# DD2090_4CAM_FFC_Connector_A.net
KiCad netlist of a schematic drawn in Altium Designer
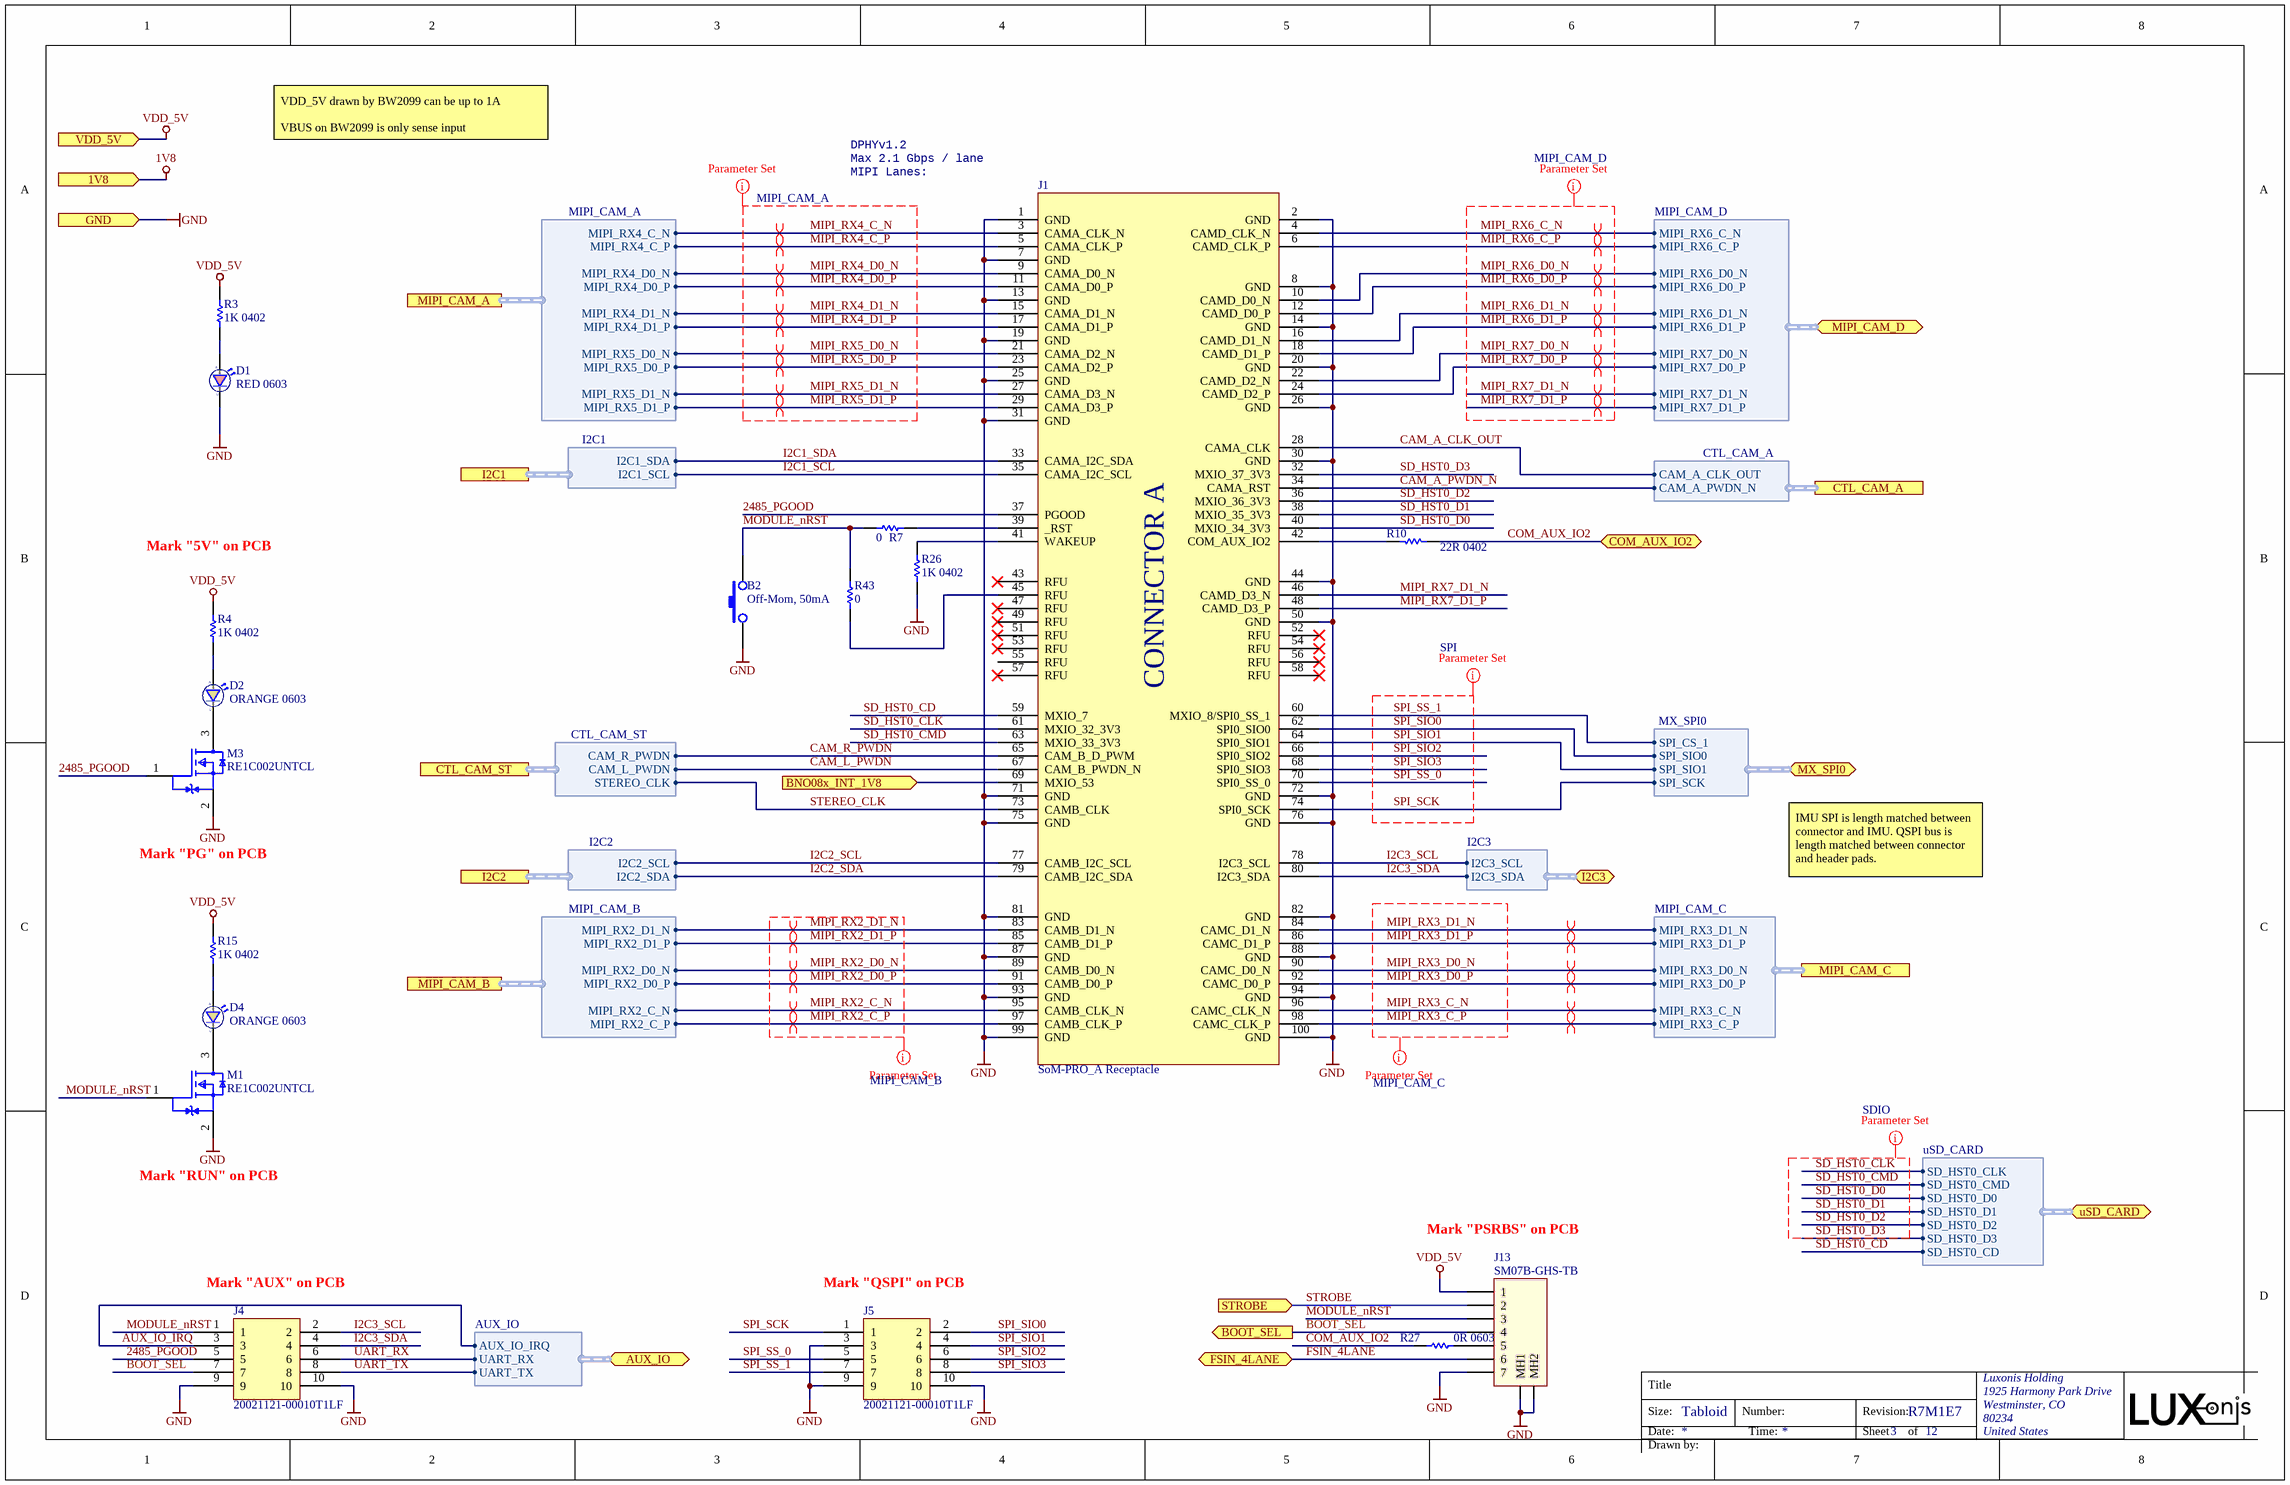
[diagram p0: DD2090_4CAM_FFC_Connector_A.SchDoc]

(export (version "E")
  (design (tool "Eeschema 10.0.6"))
  (components
    (comp (ref "B2")
      (value "Off-Mom, 50mA")
      (footprint "LuxonisMaster:DTSM-32N-V")
      (description "SWITCH TACTILE SMT 3.5mm * 6mm , brown 160gf")
      (libsource (lib "LuxonisMaster") (part "DTSM-32N-V"))
    )
    (comp (ref "D1")
      (value "RED 0603")
      (footprint "LuxonisMaster:SML_D1xx8W")
      (description "LED RED DIFFUSED 0603 SMD Red 620nm LED Indication - Discrete 2.2V 0603 (1608 Metric)")
      (libsource (lib "LuxonisMaster") (part "SML-D12U8WT86"))
    )
    (comp (ref "D2")
      (value "ORANGE 0603")
      (footprint "LuxonisMaster:SML_D1xx8W")
      (description "LED ORANGE DIFFUSED 0603 SMD Orange 605nm LED Indication - Discrete 2.2V 0603 (1608 Metric)")
      (libsource (lib "LuxonisMaster") (part "SML-D12D8WT86"))
    )
    (comp (ref "D4")
      (value "ORANGE 0603")
      (footprint "LuxonisMaster:SML_D1xx8W")
      (description "LED ORANGE DIFFUSED 0603 SMD Orange 605nm LED Indication - Discrete 2.2V 0603 (1608 Metric)")
      (libsource (lib "LuxonisMaster") (part "SML-D12D8WT86"))
    )
    (comp (ref "J1")
      (value "SoM-PRO_A Receptacle")
      (footprint "LuxonisMaster:CON_A_BW2099_SoM_DF40HC-3.0-100DS-0.4V_minpad")
      (description "CONN RCPT 100POS 0.4MM SMD GOLD")
      (libsource (lib "LuxonisMaster") (part "DF40HC(3.0)-100DS-0.4V_SoM-PRO_A"))
    )
    (comp (ref "J4")
      (value "20021121-00010T1LF")
      (footprint "LuxonisMaster:20021121-00010T1LF")
      (description "CONN HEADER SMD 10POS 1.27MM")
      (libsource (lib "LuxonisMaster") (part "20021121-00010T1LF"))
    )
    (comp (ref "J5")
      (value "20021121-00010T1LF")
      (footprint "LuxonisMaster:20021121-00010T1LF")
      (description "CONN HEADER SMD 10POS 1.27MM")
      (libsource (lib "LuxonisMaster") (part "20021121-00010T1LF"))
    )
    (comp (ref "J13")
      (value "SM07B-GHS-TB")
      (footprint "SM07B-GHS-TB")
      (description "Conn Shrouded Header HDR 7 POS 1.25mm Solder RA Side Entry SMD T/R")
      (libsource (lib "DD2090_4CAM_FFC") (part "SM07B-GHS-TB(LF)(SN)"))
    )
    (comp (ref "M1")
      (value "RE1C002UNTCL")
      (footprint "LuxonisMaster:RE1C002UNTCL")
      (description "MOSFET N-CH 20V 0.2A EMT3")
      (libsource (lib "LuxonisMaster") (part "RE1C002UNTCL"))
    )
    (comp (ref "M3")
      (value "RE1C002UNTCL")
      (footprint "LuxonisMaster:RE1C002UNTCL")
      (description "MOSFET N-CH 20V 0.2A EMT3")
      (libsource (lib "LuxonisMaster") (part "RE1C002UNTCL"))
    )
    (comp (ref "R3")
      (value "1K 0402")
      (footprint "RES_Altium_Vault_Generic:RESC0402(1005)_N")
      (fields (field (name "TOLERANCE") "1%"))
      (libsource (lib "LuxonisMaster") (part "RC0402FR-071KL"))
    )
    (comp (ref "R4")
      (value "1K 0402")
      (footprint "RES_Altium_Vault_Generic:RESC0402(1005)_N")
      (fields (field (name "TOLERANCE") "1%"))
      (libsource (lib "LuxonisMaster") (part "RC0402FR-071KL"))
    )
    (comp (ref "R7")
      (value "0")
      (footprint "RESC0402(1005)_L")
      (description "RES SMD 0 OHM JUMPER 1/16W 0402")
      (fields (field (name "TOLERANCE") "5%") (field (name "Comment") "CRCW04020000Z0ED"))
      (libsource (lib "Luxonis LLC") (part "CR0402-FX-2492GLF"))
    )
    (comp (ref "R10")
      (value "22R 0402")
      (footprint "RESC0402(1005)_N")
      (description "RES SMD 22 OHM 1% 1/16W 0402")
      (fields (field (name "TOLERANCE") "1%"))
      (libsource (lib "BW2098POE") (part "RC0402FR-0722RL"))
    )
    (comp (ref "R15")
      (value "1K 0402")
      (footprint "RES_Altium_Vault_Generic:RESC0402(1005)_N")
      (fields (field (name "TOLERANCE") "1%"))
      (libsource (lib "LuxonisMaster") (part "RC0402FR-071KL"))
    )
    (comp (ref "R26")
      (value "1K 0402")
      (footprint "RES_Altium_Vault_Generic:RESC0402(1005)_N")
      (fields (field (name "TOLERANCE") "1%"))
      (libsource (lib "LuxonisMaster") (part "RC0402FR-071KL"))
    )
    (comp (ref "R27")
      (value "0R 0603")
      (footprint "RESC0603(1608)_N")
      (fields (field (name "TOLERANCE") "5%"))
      (libsource (lib "LuxonisMaster") (part "CRCW06030000Z0EA"))
    )
    (comp (ref "R43")
      (value "0")
      (footprint "RESC0402(1005)_L")
      (description "RES SMD 0 OHM JUMPER 1/16W 0402")
      (fields (field (name "TOLERANCE") "5%") (field (name "Comment") "CRCW04020000Z0ED"))
      (libsource (lib "Luxonis LLC") (part "CR0402-FX-2492GLF"))
    )
  )
  (nets
    (net (code "13") (name "/2485_PGOOD") (class "Default")
      (node (ref "J1") (pin "37") (pinfunction "PGOOD_37") (pintype "passive"))
      (node (ref "J4") (pin "5") (pinfunction "5_5") (pintype "passive"))
      (node (ref "M3") (pin "1") (pinfunction "Gate_1") (pintype "passive"))
    )
    (net (code "14") (name "/AUX_IO_IRQ") (class "Default")
      (node (ref "J4") (pin "3") (pinfunction "3_3") (pintype "passive"))
    )
    (net (code "15") (name "/BNO08x_INT_1V8") (class "Default")
      (node (ref "J1") (pin "69") (pinfunction "MXIO_53_69") (pintype "passive"))
    )
    (net (code "16") (name "/BOOT_SEL") (class "Default")
      (node (ref "J13") (pin "4") (pinfunction "4_4") (pintype "passive"))
      (node (ref "J4") (pin "7") (pinfunction "7_7") (pintype "passive"))
    )
    (net (code "17") (name "/CAM_A_CLK_OUT") (class "Default")
      (node (ref "J1") (pin "28") (pinfunction "CAMA_CLK_28") (pintype "passive"))
    )
    (net (code "18") (name "/CAM_A_PWDN_N") (class "Default")
      (node (ref "J1") (pin "34") (pinfunction "CAMA_RST_34") (pintype "passive"))
    )
    (net (code "19") (name "/CAM_L_PWDN") (class "Default")
      (node (ref "J1") (pin "67") (pinfunction "CAM_B_PWDN_N_67") (pintype "passive"))
    )
    (net (code "20") (name "/CAM_R_PWDN") (class "Default")
      (node (ref "J1") (pin "65") (pinfunction "CAM_B_D_PWM_65") (pintype "passive"))
    )
    (net (code "21") (name "/COM_AUX_IO2") (class "Default")
      (node (ref "R10") (pin "1") (pinfunction "1_1") (pintype "passive"))
      (node (ref "R27") (pin "1") (pinfunction "1_1") (pintype "passive"))
    )
    (net (code "22") (name "/FSIN_4LANE") (class "Default")
      (node (ref "J13") (pin "6") (pinfunction "6_6") (pintype "passive"))
    )
    (net (code "23") (name "/I2C1_SCL") (class "Default")
      (node (ref "J1") (pin "35") (pinfunction "CAMA_I2C_SCL_35") (pintype "passive"))
    )
    (net (code "24") (name "/I2C1_SDA") (class "Default")
      (node (ref "J1") (pin "33") (pinfunction "CAMA_I2C_SDA_33") (pintype "passive"))
    )
    (net (code "25") (name "/I2C2_SCL") (class "Default")
      (node (ref "J1") (pin "77") (pinfunction "CAMB_I2C_SCL_77") (pintype "passive"))
    )
    (net (code "26") (name "/I2C2_SDA") (class "Default")
      (node (ref "J1") (pin "79") (pinfunction "CAMB_I2C_SDA_79") (pintype "passive"))
    )
    (net (code "27") (name "/I2C3_SCL") (class "Default")
      (node (ref "J1") (pin "78") (pinfunction "I2C3_SCL_78") (pintype "passive"))
      (node (ref "J4") (pin "2") (pinfunction "2_2") (pintype "passive"))
    )
    (net (code "28") (name "/I2C3_SDA") (class "Default")
      (node (ref "J1") (pin "80") (pinfunction "I2C3_SDA_80") (pintype "passive"))
      (node (ref "J4") (pin "4") (pinfunction "4_4") (pintype "passive"))
    )
    (net (code "29") (name "/MIPI_RX2_C_N") (class "Default")
      (node (ref "J1") (pin "95") (pinfunction "CAMB_CLK_N_95") (pintype "passive"))
    )
    (net (code "30") (name "/MIPI_RX2_C_P") (class "Default")
      (node (ref "J1") (pin "97") (pinfunction "CAMB_CLK_P_97") (pintype "passive"))
    )
    (net (code "31") (name "/MIPI_RX2_D0_N") (class "Default")
      (node (ref "J1") (pin "89") (pinfunction "CAMB_D0_N_89") (pintype "passive"))
    )
    (net (code "32") (name "/MIPI_RX2_D0_P") (class "Default")
      (node (ref "J1") (pin "91") (pinfunction "CAMB_D0_P_91") (pintype "passive"))
    )
    (net (code "33") (name "/MIPI_RX2_D1_N") (class "Default")
      (node (ref "J1") (pin "83") (pinfunction "CAMB_D1_N_83") (pintype "passive"))
    )
    (net (code "34") (name "/MIPI_RX2_D1_P") (class "Default")
      (node (ref "J1") (pin "85") (pinfunction "CAMB_D1_P_85") (pintype "passive"))
    )
    (net (code "35") (name "/MIPI_RX3_C_N") (class "Default")
      (node (ref "J1") (pin "96") (pinfunction "CAMC_CLK_N_96") (pintype "passive"))
    )
    (net (code "36") (name "/MIPI_RX3_C_P") (class "Default")
      (node (ref "J1") (pin "98") (pinfunction "CAMC_CLK_P_98") (pintype "passive"))
    )
    (net (code "37") (name "/MIPI_RX3_D0_N") (class "Default")
      (node (ref "J1") (pin "90") (pinfunction "CAMC_D0_N_90") (pintype "passive"))
    )
    (net (code "38") (name "/MIPI_RX3_D0_P") (class "Default")
      (node (ref "J1") (pin "92") (pinfunction "CAMC_D0_P_92") (pintype "passive"))
    )
    (net (code "39") (name "/MIPI_RX3_D1_N") (class "Default")
      (node (ref "J1") (pin "84") (pinfunction "CAMC_D1_N_84") (pintype "passive"))
    )
    (net (code "40") (name "/MIPI_RX3_D1_P") (class "Default")
      (node (ref "J1") (pin "86") (pinfunction "CAMC_D1_P_86") (pintype "passive"))
    )
    (net (code "41") (name "/MIPI_RX4_C_N") (class "Default")
      (node (ref "J1") (pin "3") (pinfunction "CAMA_CLK_N_3") (pintype "passive"))
    )
    (net (code "42") (name "/MIPI_RX4_C_P") (class "Default")
      (node (ref "J1") (pin "5") (pinfunction "CAMA_CLK_P_5") (pintype "passive"))
    )
    (net (code "43") (name "/MIPI_RX4_D0_N") (class "Default")
      (node (ref "J1") (pin "9") (pinfunction "CAMA_D0_N_9") (pintype "passive"))
    )
    (net (code "44") (name "/MIPI_RX4_D0_P") (class "Default")
      (node (ref "J1") (pin "11") (pinfunction "CAMA_D0_P_11") (pintype "passive"))
    )
    (net (code "45") (name "/MIPI_RX4_D1_N") (class "Default")
      (node (ref "J1") (pin "15") (pinfunction "CAMA_D1_N_15") (pintype "passive"))
    )
    (net (code "46") (name "/MIPI_RX4_D1_P") (class "Default")
      (node (ref "J1") (pin "17") (pinfunction "CAMA_D1_P_17") (pintype "passive"))
    )
    (net (code "47") (name "/MIPI_RX5_D0_N") (class "Default")
      (node (ref "J1") (pin "21") (pinfunction "CAMA_D2_N_21") (pintype "passive"))
    )
    (net (code "48") (name "/MIPI_RX5_D0_P") (class "Default")
      (node (ref "J1") (pin "23") (pinfunction "CAMA_D2_P_23") (pintype "passive"))
    )
    (net (code "49") (name "/MIPI_RX5_D1_N") (class "Default")
      (node (ref "J1") (pin "27") (pinfunction "CAMA_D3_N_27") (pintype "passive"))
    )
    (net (code "50") (name "/MIPI_RX5_D1_P") (class "Default")
      (node (ref "J1") (pin "29") (pinfunction "CAMA_D3_P_29") (pintype "passive"))
    )
    (net (code "51") (name "/MIPI_RX6_C_N") (class "Default")
      (node (ref "J1") (pin "4") (pinfunction "CAMD_CLK_N_4") (pintype "passive"))
    )
    (net (code "52") (name "/MIPI_RX6_C_P") (class "Default")
      (node (ref "J1") (pin "6") (pinfunction "CAMD_CLK_P_6") (pintype "passive"))
    )
    (net (code "53") (name "/MIPI_RX6_D0_N") (class "Default")
      (node (ref "J1") (pin "10") (pinfunction "CAMD_D0_N_10") (pintype "passive"))
    )
    (net (code "54") (name "/MIPI_RX6_D0_P") (class "Default")
      (node (ref "J1") (pin "12") (pinfunction "CAMD_D0_P_12") (pintype "passive"))
    )
    (net (code "55") (name "/MIPI_RX6_D1_N") (class "Default")
      (node (ref "J1") (pin "16") (pinfunction "CAMD_D1_N_16") (pintype "passive"))
    )
    (net (code "56") (name "/MIPI_RX6_D1_P") (class "Default")
      (node (ref "J1") (pin "18") (pinfunction "CAMD_D1_P_18") (pintype "passive"))
    )
    (net (code "57") (name "/MIPI_RX7_D0_N") (class "Default")
      (node (ref "J1") (pin "22") (pinfunction "CAMD_D2_N_22") (pintype "passive"))
    )
    (net (code "58") (name "/MIPI_RX7_D0_P") (class "Default")
      (node (ref "J1") (pin "24") (pinfunction "CAMD_D2_P_24") (pintype "passive"))
    )
    (net (code "59") (name "/MIPI_RX7_D1_N") (class "Default")
      (node (ref "J1") (pin "46") (pinfunction "CAMD_D3_N_46") (pintype "passive"))
    )
    (net (code "60") (name "/MIPI_RX7_D1_P") (class "Default")
      (node (ref "J1") (pin "48") (pinfunction "CAMD_D3_P_48") (pintype "passive"))
    )
    (net (code "61") (name "/MODULE_nRST") (class "Default")
      (node (ref "B2") (pin "2") (pinfunction "2_2") (pintype "passive"))
      (node (ref "J13") (pin "3") (pinfunction "3_3") (pintype "passive"))
      (node (ref "J4") (pin "1") (pinfunction "1_1") (pintype "passive"))
      (node (ref "M1") (pin "1") (pinfunction "Gate_1") (pintype "passive"))
      (node (ref "R43") (pin "2") (pinfunction "2_2") (pintype "passive"))
      (node (ref "R7") (pin "2") (pinfunction "2_2") (pintype "passive"))
    )
    (net (code "62") (name "/SD_HST0_CD") (class "Default")
      (node (ref "J1") (pin "59") (pinfunction "MXIO_7_59") (pintype "passive"))
    )
    (net (code "63") (name "/SD_HST0_CLK") (class "Default")
      (node (ref "J1") (pin "61") (pinfunction "MXIO_32_3V3_61") (pintype "passive"))
    )
    (net (code "64") (name "/SD_HST0_CMD") (class "Default")
      (node (ref "J1") (pin "63") (pinfunction "MXIO_33_3V3_63") (pintype "passive"))
    )
    (net (code "65") (name "/SD_HST0_D0") (class "Default")
      (node (ref "J1") (pin "40") (pinfunction "MXIO_34_3V3_40") (pintype "passive"))
    )
    (net (code "66") (name "/SD_HST0_D1") (class "Default")
      (node (ref "J1") (pin "38") (pinfunction "MXIO_35_3V3_38") (pintype "passive"))
    )
    (net (code "67") (name "/SD_HST0_D2") (class "Default")
      (node (ref "J1") (pin "36") (pinfunction "MXIO_36_3V3_36") (pintype "passive"))
    )
    (net (code "68") (name "/SD_HST0_D3") (class "Default")
      (node (ref "J1") (pin "32") (pinfunction "MXIO_37_3V3_32") (pintype "passive"))
    )
    (net (code "69") (name "/SPI_SCK") (class "Default")
      (node (ref "J1") (pin "74") (pinfunction "SPI0_SCK_74") (pintype "passive"))
      (node (ref "J5") (pin "1") (pinfunction "1_1") (pintype "passive"))
    )
    (net (code "70") (name "/SPI_SIO0") (class "Default")
      (node (ref "J1") (pin "62") (pinfunction "SPI0_SIO0_62") (pintype "passive"))
      (node (ref "J5") (pin "2") (pinfunction "2_2") (pintype "passive"))
    )
    (net (code "71") (name "/SPI_SIO1") (class "Default")
      (node (ref "J1") (pin "64") (pinfunction "SPI0_SIO1_64") (pintype "passive"))
      (node (ref "J5") (pin "4") (pinfunction "4_4") (pintype "passive"))
    )
    (net (code "72") (name "/SPI_SIO2") (class "Default")
      (node (ref "J1") (pin "66") (pinfunction "SPI0_SIO2_66") (pintype "passive"))
      (node (ref "J5") (pin "6") (pinfunction "6_6") (pintype "passive"))
    )
    (net (code "73") (name "/SPI_SIO3") (class "Default")
      (node (ref "J1") (pin "68") (pinfunction "SPI0_SIO3_68") (pintype "passive"))
      (node (ref "J5") (pin "8") (pinfunction "8_8") (pintype "passive"))
    )
    (net (code "74") (name "/SPI_SS_0") (class "Default")
      (node (ref "J1") (pin "70") (pinfunction "SPI0_SS_0_70") (pintype "passive"))
      (node (ref "J5") (pin "5") (pinfunction "5_5") (pintype "passive"))
    )
    (net (code "75") (name "/SPI_SS_1") (class "Default")
      (node (ref "J1") (pin "60") (pinfunction "MXIO_8/SPI0_SS_1_60") (pintype "passive"))
      (node (ref "J5") (pin "7") (pinfunction "7_7") (pintype "passive"))
    )
    (net (code "76") (name "/STEREO_CLK") (class "Default")
      (node (ref "J1") (pin "73") (pinfunction "CAMB_CLK_73") (pintype "passive"))
    )
    (net (code "77") (name "/STROBE") (class "Default")
      (node (ref "J13") (pin "2") (pinfunction "2_2") (pintype "passive"))
    )
    (net (code "78") (name "/UART_RX") (class "Default")
      (node (ref "J4") (pin "6") (pinfunction "6_6") (pintype "passive"))
    )
    (net (code "79") (name "/UART_TX") (class "Default")
      (node (ref "J4") (pin "8") (pinfunction "8_8") (pintype "passive"))
    )
    (net (code "93") (name "GND") (class "Default")
      (node (ref "B2") (pin "1") (pinfunction "1_1") (pintype "passive"))
      (node (ref "D1") (pin "1") (pinfunction "C_1") (pintype "passive"))
      (node (ref "J1") (pin "1") (pinfunction "GND_1") (pintype "passive"))
      (node (ref "J1") (pin "100") (pinfunction "GND_100") (pintype "passive"))
      (node (ref "J1") (pin "13") (pinfunction "GND_13") (pintype "passive"))
      (node (ref "J1") (pin "14") (pinfunction "GND_14") (pintype "passive"))
      (node (ref "J1") (pin "19") (pinfunction "GND_19") (pintype "passive"))
      (node (ref "J1") (pin "2") (pinfunction "GND_2") (pintype "passive"))
      (node (ref "J1") (pin "20") (pinfunction "GND_20") (pintype "passive"))
      (node (ref "J1") (pin "25") (pinfunction "GND_25") (pintype "passive"))
      (node (ref "J1") (pin "26") (pinfunction "GND_26") (pintype "passive"))
      (node (ref "J1") (pin "30") (pinfunction "GND_30") (pintype "passive"))
      (node (ref "J1") (pin "31") (pinfunction "GND_31") (pintype "passive"))
      (node (ref "J1") (pin "44") (pinfunction "GND_44") (pintype "passive"))
      (node (ref "J1") (pin "50") (pinfunction "GND_50") (pintype "passive"))
      (node (ref "J1") (pin "7") (pinfunction "GND_7") (pintype "passive"))
      (node (ref "J1") (pin "71") (pinfunction "GND_71") (pintype "passive"))
      (node (ref "J1") (pin "72") (pinfunction "GND_72") (pintype "passive"))
      (node (ref "J1") (pin "75") (pinfunction "GND_75") (pintype "passive"))
      (node (ref "J1") (pin "76") (pinfunction "GND_76") (pintype "passive"))
      (node (ref "J1") (pin "8") (pinfunction "GND_8") (pintype "passive"))
      (node (ref "J1") (pin "81") (pinfunction "GND_81") (pintype "passive"))
      (node (ref "J1") (pin "82") (pinfunction "GND_82") (pintype "passive"))
      (node (ref "J1") (pin "87") (pinfunction "GND_87") (pintype "passive"))
      (node (ref "J1") (pin "88") (pinfunction "GND_88") (pintype "passive"))
      (node (ref "J1") (pin "93") (pinfunction "GND_93") (pintype "passive"))
      (node (ref "J1") (pin "94") (pinfunction "GND_94") (pintype "passive"))
      (node (ref "J1") (pin "99") (pinfunction "GND_99") (pintype "passive"))
      (node (ref "J13") (pin "7") (pinfunction "7_7") (pintype "passive"))
      (node (ref "J13") (pin "MH1") (pinfunction "MH1_MH1") (pintype "passive"))
      (node (ref "J13") (pin "MH2") (pinfunction "MH2_MH2") (pintype "passive"))
      (node (ref "J4") (pin "10") (pinfunction "10_10") (pintype "passive"))
      (node (ref "J4") (pin "9") (pinfunction "9_9") (pintype "passive"))
      (node (ref "J5") (pin "10") (pinfunction "10_10") (pintype "passive"))
      (node (ref "J5") (pin "3") (pinfunction "3_3") (pintype "passive"))
      (node (ref "J5") (pin "9") (pinfunction "9_9") (pintype "passive"))
      (node (ref "M1") (pin "2") (pinfunction "Source_2") (pintype "passive"))
      (node (ref "M3") (pin "2") (pinfunction "Source_2") (pintype "passive"))
      (node (ref "R26") (pin "1") (pinfunction "1_1") (pintype "passive"))
    )
    (net (code "94") (name "Net-(D1-A)") (class "Default")
      (node (ref "D1") (pin "2") (pinfunction "A_2") (pintype "passive"))
      (node (ref "R3") (pin "1") (pinfunction "1_1") (pintype "passive"))
    )
    (net (code "95") (name "Net-(D2-A)") (class "Default")
      (node (ref "D2") (pin "2") (pinfunction "A_2") (pintype "passive"))
      (node (ref "R4") (pin "1") (pinfunction "1_1") (pintype "passive"))
    )
    (net (code "96") (name "Net-(D2-C)") (class "Default")
      (node (ref "D2") (pin "1") (pinfunction "C_1") (pintype "passive"))
      (node (ref "M3") (pin "3") (pinfunction "Drain_3") (pintype "passive"))
    )
    (net (code "97") (name "Net-(D4-A)") (class "Default")
      (node (ref "D4") (pin "2") (pinfunction "A_2") (pintype "passive"))
      (node (ref "R15") (pin "1") (pinfunction "1_1") (pintype "passive"))
    )
    (net (code "98") (name "Net-(D4-C)") (class "Default")
      (node (ref "D4") (pin "1") (pinfunction "C_1") (pintype "passive"))
      (node (ref "M1") (pin "3") (pinfunction "Drain_3") (pintype "passive"))
    )
    (net (code "99") (name "Net-(J1-COM_AUX_IO2)") (class "Default")
      (node (ref "J1") (pin "42") (pinfunction "COM_AUX_IO2_42") (pintype "passive"))
      (node (ref "R10") (pin "2") (pinfunction "2_2") (pintype "passive"))
    )
    (net (code "100") (name "Net-(J1-RFU-Pad45)") (class "Default")
      (node (ref "J1") (pin "45") (pinfunction "RFU_45") (pintype "passive"))
      (node (ref "R43") (pin "1") (pinfunction "1_1") (pintype "passive"))
    )
    (net (code "101") (name "Net-(J1-WAKEUP)") (class "Default")
      (node (ref "J1") (pin "41") (pinfunction "WAKEUP_41") (pintype "passive"))
      (node (ref "R26") (pin "2") (pinfunction "2_2") (pintype "passive"))
    )
    (net (code "102") (name "Net-(J1-_RST)") (class "Default")
      (node (ref "J1") (pin "39") (pinfunction "_RST_39") (pintype "passive"))
      (node (ref "R7") (pin "1") (pinfunction "1_1") (pintype "passive"))
    )
    (net (code "103") (name "Net-(J13-Pad5)") (class "Default")
      (node (ref "J13") (pin "5") (pinfunction "5_5") (pintype "passive"))
      (node (ref "R27") (pin "2") (pinfunction "2_2") (pintype "passive"))
    )
    (net (code "104") (name "VDD_5V") (class "Default")
      (node (ref "J13") (pin "1") (pinfunction "1_1") (pintype "passive"))
      (node (ref "R15") (pin "2") (pinfunction "2_2") (pintype "passive"))
      (node (ref "R3") (pin "2") (pinfunction "2_2") (pintype "passive"))
      (node (ref "R4") (pin "2") (pinfunction "2_2") (pintype "passive"))
    )
    (net (code "105") (name "unconnected-(J1-RFU-Pad43)") (class "Default")
      (node (ref "J1") (pin "43") (pinfunction "RFU_43") (pintype "passive+no_connect"))
    )
    (net (code "106") (name "unconnected-(J1-RFU-Pad47)") (class "Default")
      (node (ref "J1") (pin "47") (pinfunction "RFU_47") (pintype "passive+no_connect"))
    )
    (net (code "107") (name "unconnected-(J1-RFU-Pad49)") (class "Default")
      (node (ref "J1") (pin "49") (pinfunction "RFU_49") (pintype "passive+no_connect"))
    )
    (net (code "108") (name "unconnected-(J1-RFU-Pad51)") (class "Default")
      (node (ref "J1") (pin "51") (pinfunction "RFU_51") (pintype "passive+no_connect"))
    )
    (net (code "109") (name "unconnected-(J1-RFU-Pad52)") (class "Default")
      (node (ref "J1") (pin "52") (pinfunction "RFU_52") (pintype "passive+no_connect"))
    )
    (net (code "110") (name "unconnected-(J1-RFU-Pad53)") (class "Default")
      (node (ref "J1") (pin "53") (pinfunction "RFU_53") (pintype "passive+no_connect"))
    )
    (net (code "111") (name "unconnected-(J1-RFU-Pad54)") (class "Default")
      (node (ref "J1") (pin "54") (pinfunction "RFU_54") (pintype "passive+no_connect"))
    )
    (net (code "112") (name "unconnected-(J1-RFU-Pad55)") (class "Default")
      (node (ref "J1") (pin "55") (pinfunction "RFU_55") (pintype "passive"))
    )
    (net (code "113") (name "unconnected-(J1-RFU-Pad56)") (class "Default")
      (node (ref "J1") (pin "56") (pinfunction "RFU_56") (pintype "passive+no_connect"))
    )
    (net (code "114") (name "unconnected-(J1-RFU-Pad57)") (class "Default")
      (node (ref "J1") (pin "57") (pinfunction "RFU_57") (pintype "passive+no_connect"))
    )
    (net (code "115") (name "unconnected-(J1-RFU-Pad58)") (class "Default")
      (node (ref "J1") (pin "58") (pinfunction "RFU_58") (pintype "passive+no_connect"))
    )
  )
)
